# Proto_shield_REV3.net
KiCad netlist of a schematic drawn in EAGLE
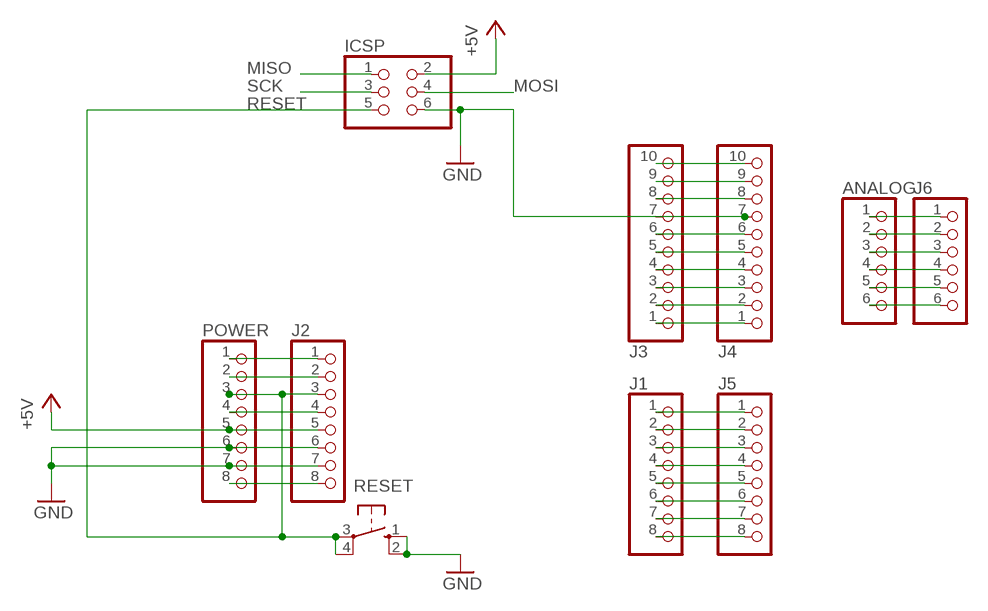
[diagram p0: schematic, sheet 1]

(export (version "E")
  (design (tool "Eeschema 10.0.6"))
  (components
    (comp (ref "ANALOG")
      (value "PINHD-1X6")
      (footprint "eagle-import:1X06")
      (libsource (lib "eagle-import") (part "PINHD-1X6"))
    )
    (comp (ref "ICSP")
      (value "PINHD-2X3")
      (footprint "eagle-import:2X03")
      (libsource (lib "eagle-import") (part "PINHD-2X3"))
    )
    (comp (ref "J1")
      (value "PINHD-1X8TH")
      (footprint "eagle-import:1X08-TH")
      (libsource (lib "eagle-import") (part "PINHD-1X8TH"))
    )
    (comp (ref "J2")
      (value "PINHD-1X8TH")
      (footprint "eagle-import:1X08-TH")
      (libsource (lib "eagle-import") (part "PINHD-1X8TH"))
    )
    (comp (ref "J3")
      (value "PINHD-1X10TH")
      (footprint "eagle-import:1X10-TH")
      (libsource (lib "eagle-import") (part "PINHD-1X10TH"))
    )
    (comp (ref "J4")
      (value "PINHD-1X10TH")
      (footprint "eagle-import:1X10-TH")
      (libsource (lib "eagle-import") (part "PINHD-1X10TH"))
    )
    (comp (ref "J5")
      (value "PINHD-1X8TH")
      (footprint "eagle-import:1X08-TH")
      (libsource (lib "eagle-import") (part "PINHD-1X8TH"))
    )
    (comp (ref "J6")
      (value "PINHD-1X6")
      (footprint "eagle-import:1X06")
      (libsource (lib "eagle-import") (part "PINHD-1X6"))
    )
    (comp (ref "POWER")
      (value "PINHD-1X8TH")
      (footprint "eagle-import:1X08-TH")
      (libsource (lib "eagle-import") (part "PINHD-1X8TH"))
    )
    (comp (ref "RESET")
      (value "10-XX")
      (footprint "eagle-import:B3F-10XX")
      (libsource (lib "eagle-import") (part "10-XX"))
    )
  )
  (nets
    (net (code "1") (name "+5V") (class "Default")
      (node (ref "ICSP") (pin "2") (pinfunction "2_2") (pintype "passive"))
      (node (ref "J2") (pin "5") (pinfunction "5_5") (pintype "passive"))
      (node (ref "POWER") (pin "5") (pinfunction "5_5") (pintype "passive"))
    )
    (net (code "2") (name "/MISO") (class "Default")
      (node (ref "ICSP") (pin "1") (pinfunction "1_1") (pintype "passive"))
    )
    (net (code "3") (name "/MOSI") (class "Default")
      (node (ref "ICSP") (pin "4") (pinfunction "4_4") (pintype "passive"))
    )
    (net (code "4") (name "/RESET") (class "Default")
      (node (ref "ICSP") (pin "5") (pinfunction "5_5") (pintype "passive"))
      (node (ref "J2") (pin "3") (pinfunction "3_3") (pintype "passive"))
      (node (ref "POWER") (pin "3") (pinfunction "3_3") (pintype "passive"))
      (node (ref "RESET") (pin "3") (pinfunction "P_3") (pintype "passive"))
      (node (ref "RESET") (pin "4") (pinfunction "P1_4") (pintype "passive"))
    )
    (net (code "5") (name "/SCK") (class "Default")
      (node (ref "ICSP") (pin "3") (pinfunction "3_3") (pintype "passive"))
    )
    (net (code "6") (name "GND") (class "Default")
      (node (ref "ICSP") (pin "6") (pinfunction "6_6") (pintype "passive"))
      (node (ref "J2") (pin "7") (pinfunction "7_7") (pintype "passive"))
      (node (ref "J3") (pin "7") (pinfunction "7_7") (pintype "passive"))
      (node (ref "J4") (pin "7") (pinfunction "7_7") (pintype "passive"))
      (node (ref "POWER") (pin "7") (pinfunction "7_7") (pintype "passive"))
      (node (ref "RESET") (pin "1") (pinfunction "S_1") (pintype "passive"))
      (node (ref "RESET") (pin "2") (pinfunction "S1_2") (pintype "passive"))
    )
    (net (code "7") (name "Net-(ANALOG-Pad1)") (class "Default")
      (node (ref "ANALOG") (pin "1") (pinfunction "1_1") (pintype "passive"))
      (node (ref "J6") (pin "1") (pinfunction "1_1") (pintype "passive"))
    )
    (net (code "8") (name "Net-(ANALOG-Pad2)") (class "Default")
      (node (ref "ANALOG") (pin "2") (pinfunction "2_2") (pintype "passive"))
      (node (ref "J6") (pin "2") (pinfunction "2_2") (pintype "passive"))
    )
    (net (code "9") (name "Net-(ANALOG-Pad3)") (class "Default")
      (node (ref "ANALOG") (pin "3") (pinfunction "3_3") (pintype "passive"))
      (node (ref "J6") (pin "3") (pinfunction "3_3") (pintype "passive"))
    )
    (net (code "10") (name "Net-(ANALOG-Pad4)") (class "Default")
      (node (ref "ANALOG") (pin "4") (pinfunction "4_4") (pintype "passive"))
      (node (ref "J6") (pin "4") (pinfunction "4_4") (pintype "passive"))
    )
    (net (code "11") (name "Net-(ANALOG-Pad5)") (class "Default")
      (node (ref "ANALOG") (pin "5") (pinfunction "5_5") (pintype "passive"))
      (node (ref "J6") (pin "5") (pinfunction "5_5") (pintype "passive"))
    )
    (net (code "12") (name "Net-(ANALOG-Pad6)") (class "Default")
      (node (ref "ANALOG") (pin "6") (pinfunction "6_6") (pintype "passive"))
      (node (ref "J6") (pin "6") (pinfunction "6_6") (pintype "passive"))
    )
    (net (code "13") (name "Net-(J1-Pad1)") (class "Default")
      (node (ref "J1") (pin "1") (pinfunction "1_1") (pintype "passive"))
      (node (ref "J5") (pin "1") (pinfunction "1_1") (pintype "passive"))
    )
    (net (code "14") (name "Net-(J1-Pad2)") (class "Default")
      (node (ref "J1") (pin "2") (pinfunction "2_2") (pintype "passive"))
      (node (ref "J5") (pin "2") (pinfunction "2_2") (pintype "passive"))
    )
    (net (code "15") (name "Net-(J1-Pad3)") (class "Default")
      (node (ref "J1") (pin "3") (pinfunction "3_3") (pintype "passive"))
      (node (ref "J5") (pin "3") (pinfunction "3_3") (pintype "passive"))
    )
    (net (code "16") (name "Net-(J1-Pad4)") (class "Default")
      (node (ref "J1") (pin "4") (pinfunction "4_4") (pintype "passive"))
      (node (ref "J5") (pin "4") (pinfunction "4_4") (pintype "passive"))
    )
    (net (code "17") (name "Net-(J1-Pad5)") (class "Default")
      (node (ref "J1") (pin "5") (pinfunction "5_5") (pintype "passive"))
      (node (ref "J5") (pin "5") (pinfunction "5_5") (pintype "passive"))
    )
    (net (code "18") (name "Net-(J1-Pad6)") (class "Default")
      (node (ref "J1") (pin "6") (pinfunction "6_6") (pintype "passive"))
      (node (ref "J5") (pin "6") (pinfunction "6_6") (pintype "passive"))
    )
    (net (code "19") (name "Net-(J1-Pad7)") (class "Default")
      (node (ref "J1") (pin "7") (pinfunction "7_7") (pintype "passive"))
      (node (ref "J5") (pin "7") (pinfunction "7_7") (pintype "passive"))
    )
    (net (code "20") (name "Net-(J1-Pad8)") (class "Default")
      (node (ref "J1") (pin "8") (pinfunction "8_8") (pintype "passive"))
      (node (ref "J5") (pin "8") (pinfunction "8_8") (pintype "passive"))
    )
    (net (code "21") (name "Net-(J2-Pad1)") (class "Default")
      (node (ref "J2") (pin "1") (pinfunction "1_1") (pintype "passive"))
      (node (ref "POWER") (pin "1") (pinfunction "1_1") (pintype "passive"))
    )
    (net (code "22") (name "Net-(J2-Pad2)") (class "Default")
      (node (ref "J2") (pin "2") (pinfunction "2_2") (pintype "passive"))
      (node (ref "POWER") (pin "2") (pinfunction "2_2") (pintype "passive"))
    )
    (net (code "23") (name "Net-(J2-Pad4)") (class "Default")
      (node (ref "J2") (pin "4") (pinfunction "4_4") (pintype "passive"))
      (node (ref "POWER") (pin "4") (pinfunction "4_4") (pintype "passive"))
    )
    (net (code "24") (name "Net-(J2-Pad6)") (class "Default")
      (node (ref "J2") (pin "6") (pinfunction "6_6") (pintype "passive"))
      (node (ref "POWER") (pin "6") (pinfunction "6_6") (pintype "passive"))
    )
    (net (code "25") (name "Net-(J2-Pad8)") (class "Default")
      (node (ref "J2") (pin "8") (pinfunction "8_8") (pintype "passive"))
      (node (ref "POWER") (pin "8") (pinfunction "8_8") (pintype "passive"))
    )
    (net (code "26") (name "Net-(J3-Pad1)") (class "Default")
      (node (ref "J3") (pin "1") (pinfunction "1_1") (pintype "passive"))
      (node (ref "J4") (pin "1") (pinfunction "1_1") (pintype "passive"))
    )
    (net (code "27") (name "Net-(J3-Pad2)") (class "Default")
      (node (ref "J3") (pin "2") (pinfunction "2_2") (pintype "passive"))
      (node (ref "J4") (pin "2") (pinfunction "2_2") (pintype "passive"))
    )
    (net (code "28") (name "Net-(J3-Pad3)") (class "Default")
      (node (ref "J3") (pin "3") (pinfunction "3_3") (pintype "passive"))
      (node (ref "J4") (pin "3") (pinfunction "3_3") (pintype "passive"))
    )
    (net (code "29") (name "Net-(J3-Pad4)") (class "Default")
      (node (ref "J3") (pin "4") (pinfunction "4_4") (pintype "passive"))
      (node (ref "J4") (pin "4") (pinfunction "4_4") (pintype "passive"))
    )
    (net (code "30") (name "Net-(J3-Pad5)") (class "Default")
      (node (ref "J3") (pin "5") (pinfunction "5_5") (pintype "passive"))
      (node (ref "J4") (pin "5") (pinfunction "5_5") (pintype "passive"))
    )
    (net (code "31") (name "Net-(J3-Pad6)") (class "Default")
      (node (ref "J3") (pin "6") (pinfunction "6_6") (pintype "passive"))
      (node (ref "J4") (pin "6") (pinfunction "6_6") (pintype "passive"))
    )
    (net (code "32") (name "Net-(J3-Pad8)") (class "Default")
      (node (ref "J3") (pin "8") (pinfunction "8_8") (pintype "passive"))
      (node (ref "J4") (pin "8") (pinfunction "8_8") (pintype "passive"))
    )
    (net (code "33") (name "Net-(J3-Pad9)") (class "Default")
      (node (ref "J3") (pin "9") (pinfunction "9_9") (pintype "passive"))
      (node (ref "J4") (pin "9") (pinfunction "9_9") (pintype "passive"))
    )
    (net (code "34") (name "Net-(J3-Pad10)") (class "Default")
      (node (ref "J3") (pin "10") (pinfunction "10_10") (pintype "passive"))
      (node (ref "J4") (pin "10") (pinfunction "10_10") (pintype "passive"))
    )
  )
)
